# fc_power_board_v2.net
KiCad netlist of a schematic drawn in EAGLE
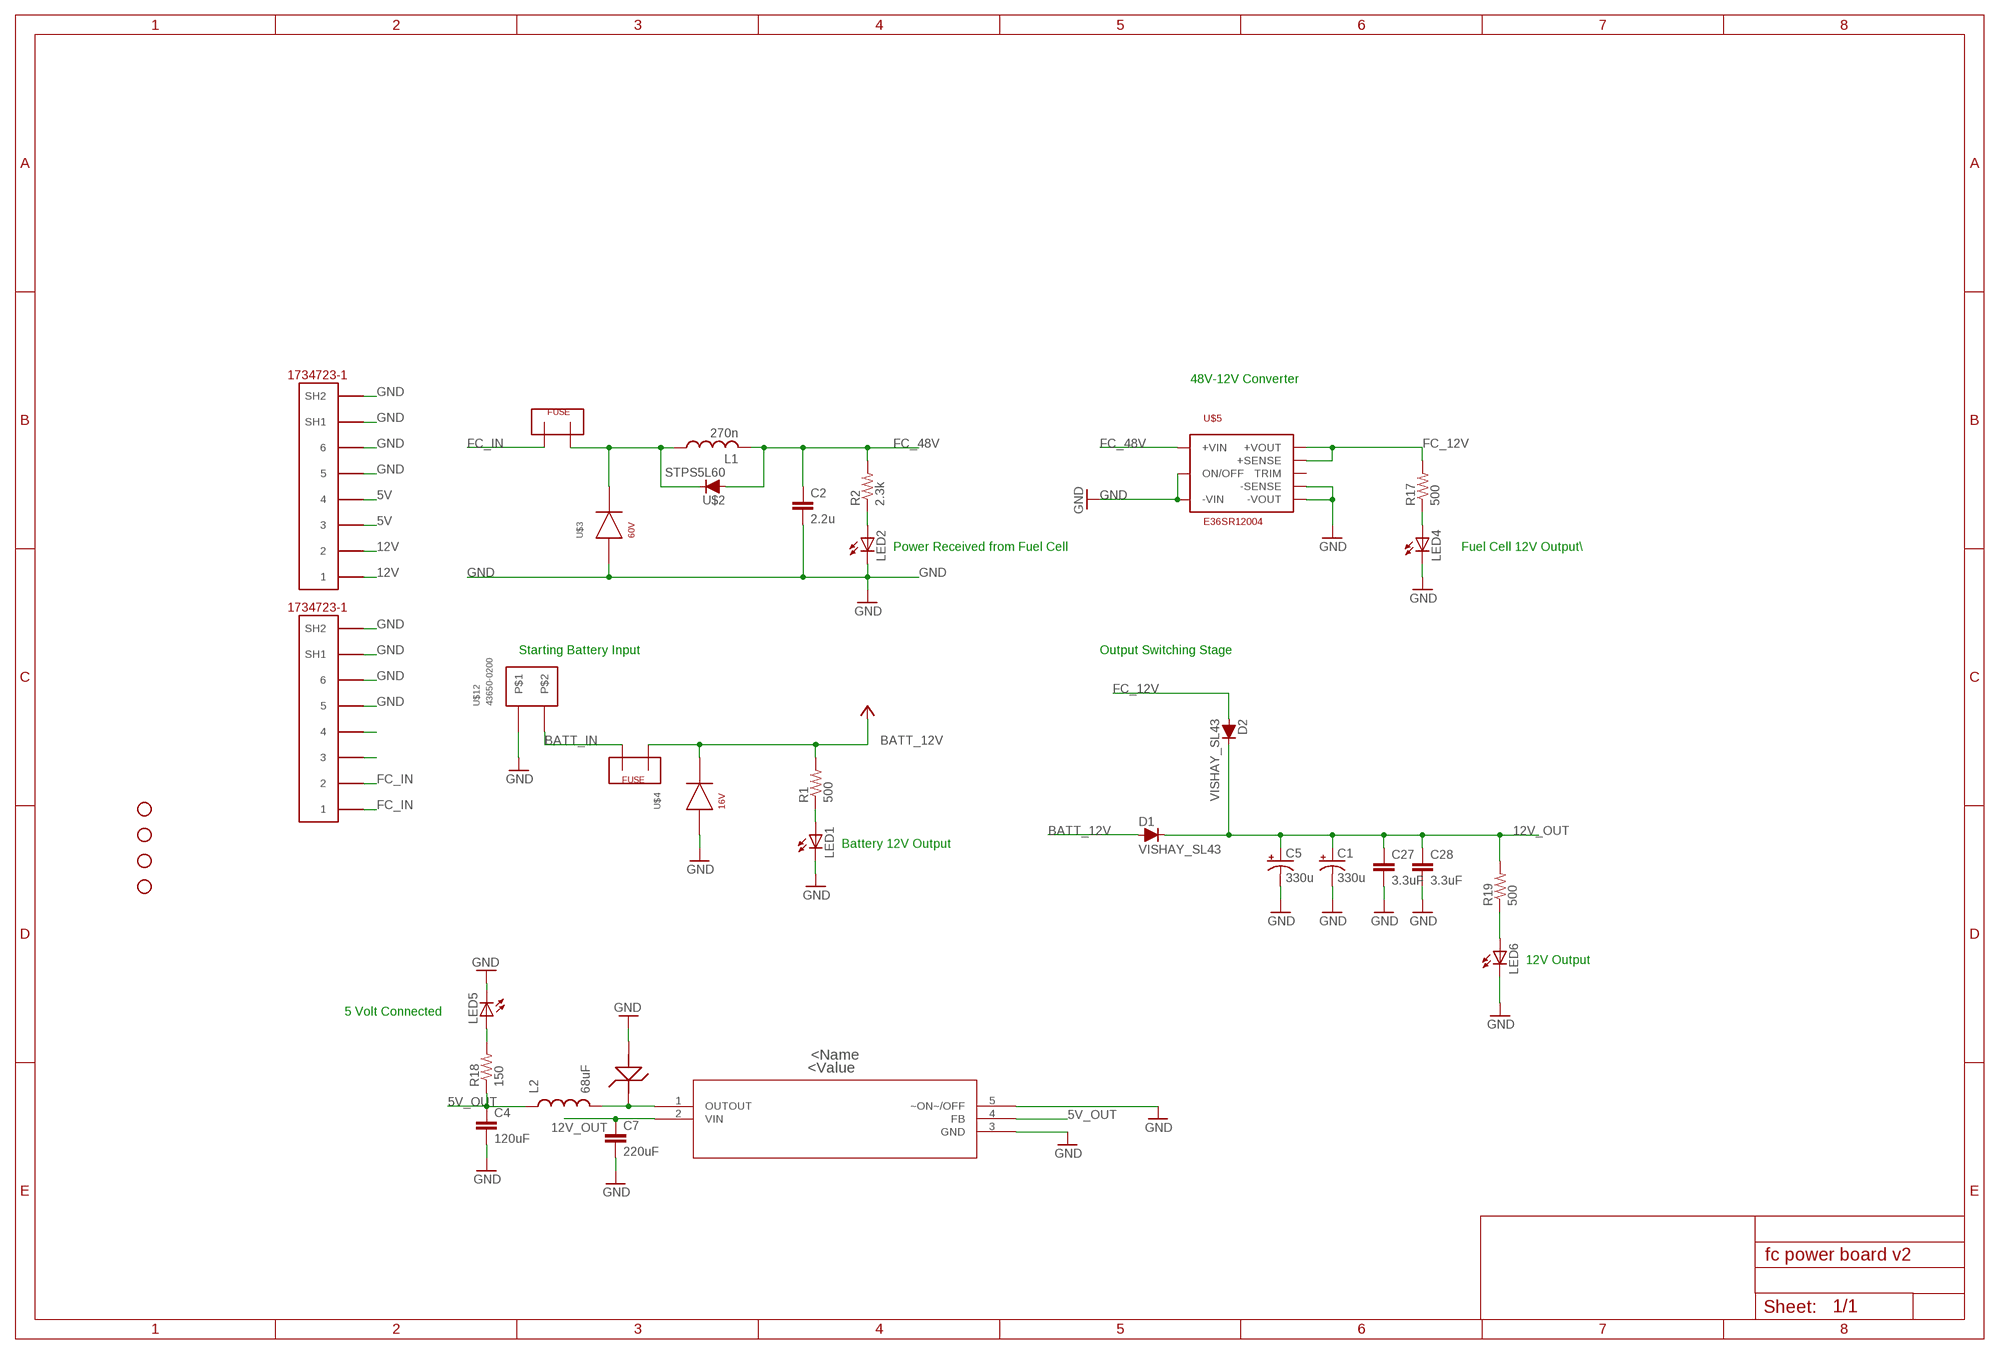
[diagram p0: schematic, sheet 1]

(export (version "E")
  (design (tool "Eeschema 10.0.6"))
  (components
    (comp (ref "C1")
      (value "330u")
      (footprint "eagle-import:PANASONIC_E")
      (libsource (lib "eagle-import") (part "CAP_POLE"))
    )
    (comp (ref "C2")
      (value "2.2u")
      (footprint "eagle-import:C1210")
      (libsource (lib "eagle-import") (part "C-EUC1210"))
    )
    (comp (ref "C4")
      (value "120uF")
      (footprint "eagle-import:0805")
      (libsource (lib "eagle-import") (part "CAP0805"))
    )
    (comp (ref "C5")
      (value "330u")
      (footprint "eagle-import:PANASONIC_E")
      (libsource (lib "eagle-import") (part "CAP_POLE"))
    )
    (comp (ref "C7")
      (value "220uF")
      (footprint "eagle-import:0805")
      (libsource (lib "eagle-import") (part "CAP0805"))
    )
    (comp (ref "C27")
      (value "3.3uF")
      (footprint "eagle-import:C0805K")
      (libsource (lib "eagle-import") (part "C-EUC0805K"))
    )
    (comp (ref "C28")
      (value "3.3uF")
      (footprint "eagle-import:C0805K")
      (libsource (lib "eagle-import") (part "C-EUC0805K"))
    )
    (comp (ref "D1")
      (value "VISHAY_SL43")
      (footprint "eagle-import:DO-214AB_SMC")
      (libsource (lib "eagle-import") (part "VISHAY_SL43"))
    )
    (comp (ref "D2")
      (value "VISHAY_SL43")
      (footprint "eagle-import:DO-214AB_SMC")
      (libsource (lib "eagle-import") (part "VISHAY_SL43"))
    )
    (comp (ref "L1")
      (value "270n")
      (footprint "eagle-import:L3225P")
      (libsource (lib "eagle-import") (part "L-USL3225P"))
    )
    (comp (ref "L2")
      (value "68uF")
      (footprint "eagle-import:0805")
      (libsource (lib "eagle-import") (part "INDUCTOR0805"))
    )
    (comp (ref "LED1")
      (value "LED1206")
      (footprint "eagle-import:LED-1206")
      (libsource (lib "eagle-import") (part "LED1206"))
    )
    (comp (ref "LED2")
      (value "LED1206")
      (footprint "eagle-import:LED-1206")
      (libsource (lib "eagle-import") (part "LED1206"))
    )
    (comp (ref "LED4")
      (value "LED1206")
      (footprint "eagle-import:LED-1206")
      (libsource (lib "eagle-import") (part "LED1206"))
    )
    (comp (ref "LED5")
      (value "LED1206")
      (footprint "eagle-import:LED-1206")
      (libsource (lib "eagle-import") (part "LED1206"))
    )
    (comp (ref "LED6")
      (value "LED1206")
      (footprint "eagle-import:LED-1206")
      (libsource (lib "eagle-import") (part "LED1206"))
    )
    (comp (ref "R1")
      (value "500")
      (footprint "eagle-import:M0805")
      (libsource (lib "eagle-import") (part "R-US_M0805"))
    )
    (comp (ref "R2")
      (value "2.3k")
      (footprint "eagle-import:M0805")
      (libsource (lib "eagle-import") (part "R-US_M0805"))
    )
    (comp (ref "R17")
      (value "500")
      (footprint "eagle-import:M0805")
      (libsource (lib "eagle-import") (part "R-US_M0805"))
    )
    (comp (ref "R18")
      (value "150")
      (footprint "eagle-import:M0805")
      (libsource (lib "eagle-import") (part "R-US_M0805"))
    )
    (comp (ref "R19")
      (value "500")
      (footprint "eagle-import:M0805")
      (libsource (lib "eagle-import") (part "R-US_M0805"))
    )
    (comp (ref "STANDOFF1")
      (value "STAND-OFF")
      (footprint "eagle-import:STAND-OFF")
      (libsource (lib "eagle-import") (part "STAND-OFF"))
    )
    (comp (ref "STANDOFF2")
      (value "STAND-OFF")
      (footprint "eagle-import:STAND-OFF")
      (libsource (lib "eagle-import") (part "STAND-OFF"))
    )
    (comp (ref "STANDOFF3")
      (value "STAND-OFF")
      (footprint "eagle-import:STAND-OFF")
      (libsource (lib "eagle-import") (part "STAND-OFF"))
    )
    (comp (ref "STANDOFF4")
      (value "STAND-OFF")
      (footprint "eagle-import:STAND-OFF")
      (libsource (lib "eagle-import") (part "STAND-OFF"))
    )
    (comp (ref "U$2")
      (value "STPS5L60")
      (footprint "eagle-import:STM_SMC")
      (libsource (lib "eagle-import") (part "STPS5L60"))
    )
    (comp (ref "U$3")
      (value "SMBJ60CA")
      (footprint "eagle-import:.277X.089")
      (libsource (lib "eagle-import") (part "SMBJ60CA"))
    )
    (comp (ref "U$4")
      (value "SMAJ16CA")
      (footprint "eagle-import:.25X.07")
      (libsource (lib "eagle-import") (part "SMAJ16CA"))
    )
    (comp (ref "U$5")
      (value "E36SR12004")
      (footprint "eagle-import:2.30X0.90X0.34")
      (libsource (lib "eagle-import") (part "E36SR12004"))
    )
    (comp (ref "U$6")
      (value "5555140-6")
      (footprint "eagle-import:1734723-1_RJ11")
      (libsource (lib "eagle-import") (part "5555140-6"))
    )
    (comp (ref "U$7")
      (value "FUSEMINI-BLADE")
      (footprint "eagle-import:MINI-BLADE-FUSE")
      (libsource (lib "eagle-import") (part "FUSEMINI-BLADE"))
    )
    (comp (ref "U$8")
      (value "LM2595T-5.0")
      (footprint "eagle-import:T05D")
      (fields
        (field (name "MANUFACTURER_PART_NUMBER") "LM2595T50")
        (field (name "COPYRIGHT") "Copyright C 2015 Accelerated Designs. All rights reserved")
      )
      (libsource (lib "eagle-import") (part "LM2595T-5.0"))
    )
    (comp (ref "U$9")
      (value "MURS120T3G")
      (footprint "eagle-import:MURS120T3G")
      (libsource (lib "eagle-import") (part "MURS120T3G"))
    )
    (comp (ref "U$10")
      (value "FUSEMINI-BLADE")
      (footprint "eagle-import:MINI-BLADE-FUSE")
      (libsource (lib "eagle-import") (part "FUSEMINI-BLADE"))
    )
    (comp (ref "U$11")
      (value "5555140-6")
      (footprint "eagle-import:1734723-1_RJ11")
      (libsource (lib "eagle-import") (part "5555140-6"))
    )
    (comp (ref "U$12")
      (value "43650-0200")
      (footprint "eagle-import:43650-0200")
      (libsource (lib "eagle-import") (part "43650-0200"))
    )
  )
  (nets
    (net (code "1") (name "+5V") (class "Default")
      (node (ref "D1") (pin "A") (pinfunction "A_A") (pintype "passive"))
      (node (ref "R1") (pin "2") (pinfunction "2_2") (pintype "passive"))
      (node (ref "U$10") (pin "OUT") (pinfunction "OUT_OUT") (pintype "bidirectional"))
      (node (ref "U$4") (pin "CATHODE") (pinfunction "CATHODE_CATHODE") (pintype "bidirectional"))
    )
    (net (code "2") (name "/5V") (class "Default")
      (node (ref "U$11") (pin "3") (pinfunction "3_3") (pintype "bidirectional"))
      (node (ref "U$11") (pin "4") (pinfunction "4_4") (pintype "bidirectional"))
    )
    (net (code "3") (name "/5V_OUT") (class "Default")
      (node (ref "C4") (pin "1") (pinfunction "1_1") (pintype "passive"))
      (node (ref "L2") (pin "1") (pinfunction "1_1") (pintype "passive"))
      (node (ref "R18") (pin "1") (pinfunction "1_1") (pintype "passive"))
      (node (ref "U$8") (pin "4") (pinfunction "FB_4") (pintype "passive"))
    )
    (net (code "4") (name "/12V") (class "Default")
      (node (ref "U$11") (pin "1") (pinfunction "1_1") (pintype "bidirectional"))
      (node (ref "U$11") (pin "2") (pinfunction "2_2") (pintype "bidirectional"))
    )
    (net (code "5") (name "/12V_OUT") (class "Default")
      (node (ref "C1") (pin "+") (pinfunction "+_+") (pintype "passive"))
      (node (ref "C27") (pin "1") (pinfunction "1_1") (pintype "passive"))
      (node (ref "C28") (pin "1") (pinfunction "1_1") (pintype "passive"))
      (node (ref "C5") (pin "+") (pinfunction "+_+") (pintype "passive"))
      (node (ref "C7") (pin "1") (pinfunction "1_1") (pintype "passive"))
      (node (ref "D1") (pin "C") (pinfunction "C_C") (pintype "passive"))
      (node (ref "D2") (pin "C") (pinfunction "C_C") (pintype "passive"))
      (node (ref "R19") (pin "2") (pinfunction "2_2") (pintype "passive"))
      (node (ref "U$8") (pin "2") (pinfunction "VIN_2") (pintype "input"))
    )
    (net (code "6") (name "/BATT_IN") (class "Default")
      (node (ref "U$10") (pin "IN") (pinfunction "IN_IN") (pintype "bidirectional"))
      (node (ref "U$12") (pin "P$1") (pinfunction "P$2_P$1") (pintype "bidirectional"))
    )
    (net (code "7") (name "/FC_12V") (class "Default")
      (node (ref "D2") (pin "A") (pinfunction "A_A") (pintype "passive"))
      (node (ref "R17") (pin "2") (pinfunction "2_2") (pintype "passive"))
      (node (ref "U$5") (pin "P$7") (pinfunction "+SENSE_P$7") (pintype "input"))
      (node (ref "U$5") (pin "P$8") (pinfunction "+VOUT_P$8") (pintype "power_in"))
    )
    (net (code "8") (name "/FC_48V") (class "Default")
      (node (ref "C2") (pin "1") (pinfunction "1_1") (pintype "passive"))
      (node (ref "L1") (pin "2") (pinfunction "2_2") (pintype "passive"))
      (node (ref "R2") (pin "2") (pinfunction "2_2") (pintype "passive"))
      (node (ref "U$2") (pin "A") (pinfunction "A_A") (pintype "passive"))
      (node (ref "U$5") (pin "P$1") (pinfunction "+VIN_P$1") (pintype "power_in"))
    )
    (net (code "9") (name "/FC_IN") (class "Default")
      (node (ref "U$6") (pin "1") (pinfunction "1_1") (pintype "bidirectional"))
      (node (ref "U$6") (pin "2") (pinfunction "2_2") (pintype "bidirectional"))
      (node (ref "U$7") (pin "OUT") (pinfunction "OUT_OUT") (pintype "bidirectional"))
    )
    (net (code "10") (name "GND") (class "Default")
      (node (ref "C1") (pin "-") (pinfunction "-_-") (pintype "passive"))
      (node (ref "C2") (pin "2") (pinfunction "2_2") (pintype "passive"))
      (node (ref "C27") (pin "2") (pinfunction "2_2") (pintype "passive"))
      (node (ref "C28") (pin "2") (pinfunction "2_2") (pintype "passive"))
      (node (ref "C4") (pin "2") (pinfunction "2_2") (pintype "passive"))
      (node (ref "C5") (pin "-") (pinfunction "-_-") (pintype "passive"))
      (node (ref "C7") (pin "2") (pinfunction "2_2") (pintype "passive"))
      (node (ref "LED1") (pin "C") (pinfunction "C_C") (pintype "passive"))
      (node (ref "LED2") (pin "C") (pinfunction "C_C") (pintype "passive"))
      (node (ref "LED4") (pin "C") (pinfunction "C_C") (pintype "passive"))
      (node (ref "LED5") (pin "C") (pinfunction "C_C") (pintype "passive"))
      (node (ref "LED6") (pin "C") (pinfunction "C_C") (pintype "passive"))
      (node (ref "U$11") (pin "5") (pinfunction "5_5") (pintype "bidirectional"))
      (node (ref "U$11") (pin "6") (pinfunction "6_6") (pintype "bidirectional"))
      (node (ref "U$11") (pin "SH1") (pinfunction "SH1_SH1") (pintype "bidirectional"))
      (node (ref "U$11") (pin "SH2") (pinfunction "SH2_SH2") (pintype "bidirectional"))
      (node (ref "U$12") (pin "P$2") (pinfunction "P$1_P$2") (pintype "bidirectional"))
      (node (ref "U$3") (pin "ANODE") (pinfunction "ANODE_ANODE") (pintype "bidirectional"))
      (node (ref "U$4") (pin "ANODE") (pinfunction "ANODE_ANODE") (pintype "bidirectional"))
      (node (ref "U$5") (pin "P$2") (pinfunction "ON/OFF_P$2") (pintype "bidirectional"))
      (node (ref "U$5") (pin "P$3") (pinfunction "-VIN_P$3") (pintype "power_in"))
      (node (ref "U$5") (pin "P$4") (pinfunction "-VOUT_P$4") (pintype "power_in"))
      (node (ref "U$5") (pin "P$5") (pinfunction "-SENSE_P$5") (pintype "input"))
      (node (ref "U$6") (pin "5") (pinfunction "5_5") (pintype "bidirectional"))
      (node (ref "U$6") (pin "6") (pinfunction "6_6") (pintype "bidirectional"))
      (node (ref "U$6") (pin "SH1") (pinfunction "SH1_SH1") (pintype "bidirectional"))
      (node (ref "U$6") (pin "SH2") (pinfunction "SH2_SH2") (pintype "bidirectional"))
      (node (ref "U$8") (pin "3") (pinfunction "GND_3") (pintype "passive"))
      (node (ref "U$8") (pin "5") (pinfunction "~{ON}/OFF_5") (pintype "passive"))
      (node (ref "U$9") (pin "P$2") (pinfunction "PIN1_P$2") (pintype "bidirectional"))
    )
    (net (code "11") (name "Net-(L1-Pad1)") (class "Default")
      (node (ref "L1") (pin "1") (pinfunction "1_1") (pintype "passive"))
      (node (ref "U$2") (pin "C") (pinfunction "C_C") (pintype "passive"))
      (node (ref "U$3") (pin "CATHODE") (pinfunction "CATHODE_CATHODE") (pintype "bidirectional"))
      (node (ref "U$7") (pin "IN") (pinfunction "IN_IN") (pintype "bidirectional"))
    )
    (net (code "12") (name "Net-(LED1-PadA)") (class "Default")
      (node (ref "LED1") (pin "A") (pinfunction "A_A") (pintype "passive"))
      (node (ref "R1") (pin "1") (pinfunction "1_1") (pintype "passive"))
    )
    (net (code "13") (name "Net-(LED2-PadA)") (class "Default")
      (node (ref "LED2") (pin "A") (pinfunction "A_A") (pintype "passive"))
      (node (ref "R2") (pin "1") (pinfunction "1_1") (pintype "passive"))
    )
    (net (code "14") (name "Net-(LED4-PadA)") (class "Default")
      (node (ref "LED4") (pin "A") (pinfunction "A_A") (pintype "passive"))
      (node (ref "R17") (pin "1") (pinfunction "1_1") (pintype "passive"))
    )
    (net (code "15") (name "Net-(LED5-PadA)") (class "Default")
      (node (ref "LED5") (pin "A") (pinfunction "A_A") (pintype "passive"))
      (node (ref "R18") (pin "2") (pinfunction "2_2") (pintype "passive"))
    )
    (net (code "16") (name "Net-(LED6-PadA)") (class "Default")
      (node (ref "LED6") (pin "A") (pinfunction "A_A") (pintype "passive"))
      (node (ref "R19") (pin "1") (pinfunction "1_1") (pintype "passive"))
    )
    (net (code "17") (name "Net-(U$8-OUTOUT)") (class "Default")
      (node (ref "L2") (pin "2") (pinfunction "2_2") (pintype "passive"))
      (node (ref "U$8") (pin "1") (pinfunction "OUTOUT_1") (pintype "output"))
      (node (ref "U$9") (pin "P$1") (pinfunction "P$2_P$1") (pintype "bidirectional"))
    )
    (net (code "18") (name "unconnected-(U$5-TRIM-PadP$6)") (class "Default")
      (node (ref "U$5") (pin "P$6") (pinfunction "TRIM_P$6") (pintype "bidirectional"))
    )
    (net (code "19") (name "unconnected-(U$6-Pad3)") (class "Default")
      (node (ref "U$6") (pin "3") (pinfunction "3_3") (pintype "bidirectional"))
    )
    (net (code "20") (name "unconnected-(U$6-Pad4)") (class "Default")
      (node (ref "U$6") (pin "4") (pinfunction "4_4") (pintype "bidirectional"))
    )
  )
)
